# HomeHeat.net
KiCad netlist of a schematic drawn in EAGLE
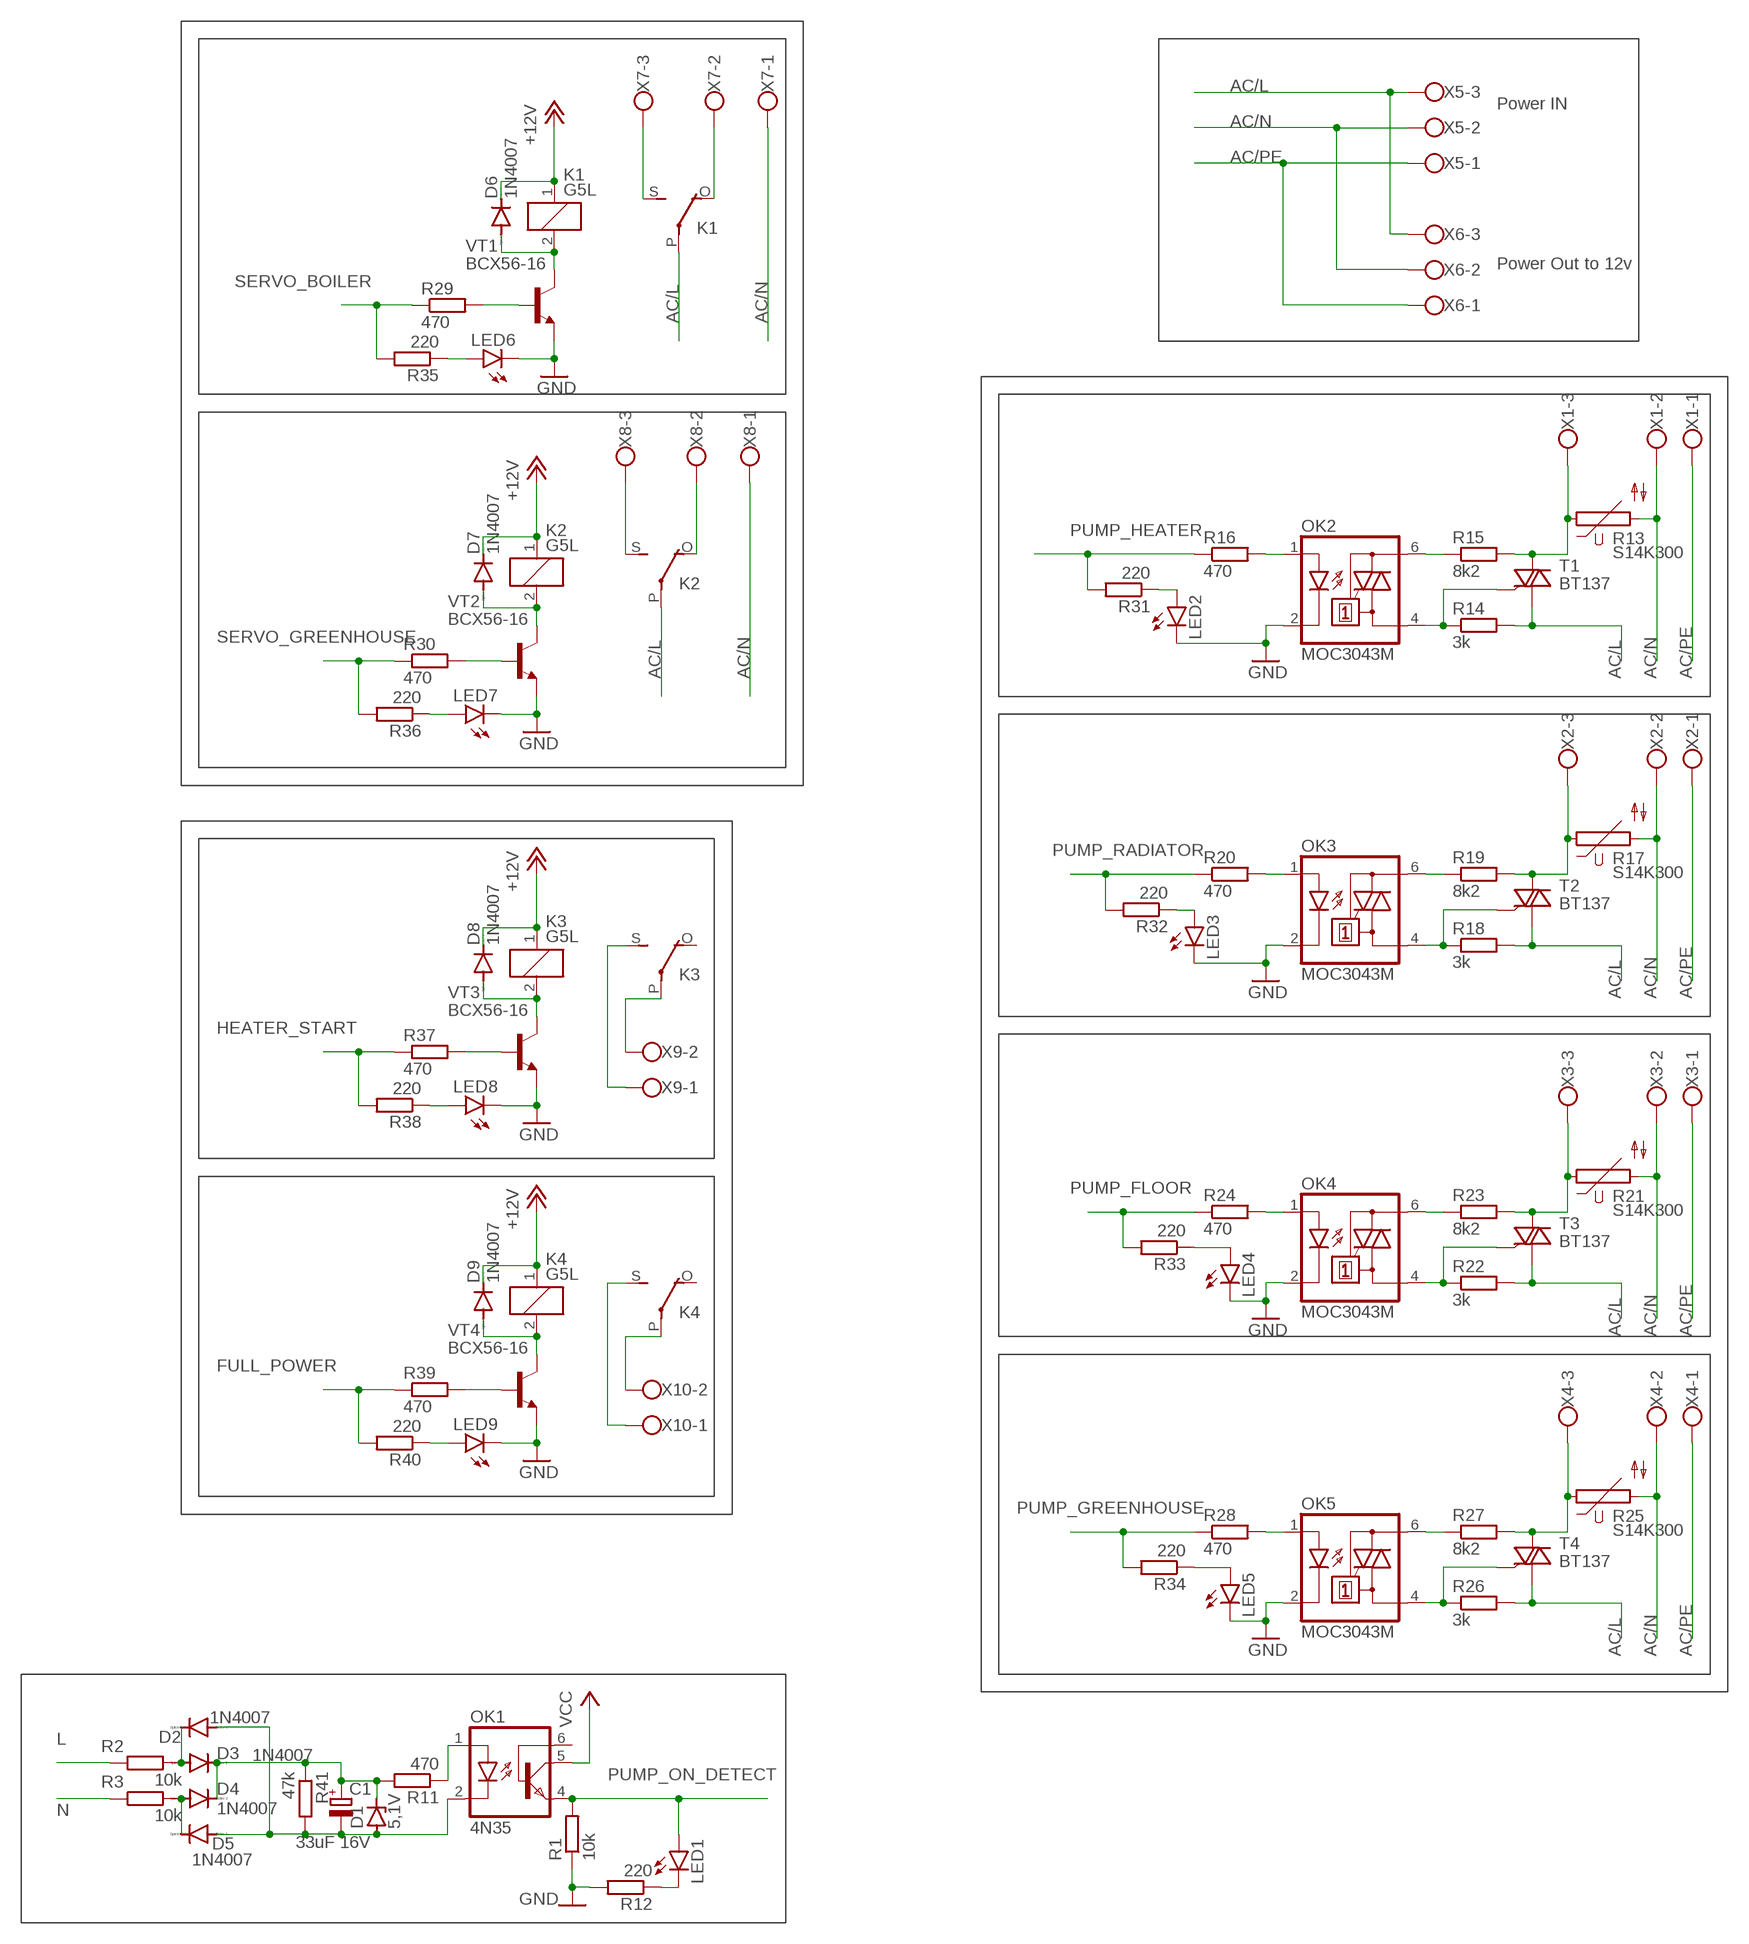
[diagram p0: schematic, sheet 1]

(export (version "E")
  (design (tool "Eeschema 10.0.6"))
  (components
    (comp (ref "C1")
      (value "33uF 16V")
      (footprint "eagle-import:SMC_A")
      (libsource (lib "eagle-import") (part "CPOL-EUSMCA"))
    )
    (comp (ref "D1")
      (value "5,1V")
      (footprint "eagle-import:DO41Z10")
      (libsource (lib "eagle-import") (part "ZENER-DIODEDO41Z10"))
    )
    (comp (ref "D2")
      (value "1N4007")
      (footprint "eagle-import:DO41-10")
      (libsource (lib "eagle-import") (part "1N4004"))
    )
    (comp (ref "D3")
      (value "1N4007")
      (footprint "eagle-import:DO41-10")
      (libsource (lib "eagle-import") (part "1N4004"))
    )
    (comp (ref "D4")
      (value "1N4007")
      (footprint "eagle-import:DO41-10")
      (fields (field (name "SPICEPREFIX") "D"))
      (libsource (lib "eagle-import") (part "1N4004"))
    )
    (comp (ref "D5")
      (value "1N4007")
      (footprint "eagle-import:DO41-10")
      (libsource (lib "eagle-import") (part "1N4004"))
    )
    (comp (ref "D6")
      (value "1N4007")
      (footprint "eagle-import:DO41-10")
      (libsource (lib "eagle-import") (part "1N4004"))
    )
    (comp (ref "D7")
      (value "1N4007")
      (footprint "eagle-import:DO41-10")
      (libsource (lib "eagle-import") (part "1N4004"))
    )
    (comp (ref "D8")
      (value "1N4007")
      (footprint "eagle-import:DO41-10")
      (libsource (lib "eagle-import") (part "1N4004"))
    )
    (comp (ref "D9")
      (value "1N4007")
      (footprint "eagle-import:DO41-10")
      (libsource (lib "eagle-import") (part "1N4004"))
    )
    (comp (ref "K1")
      (value "G5L")
      (footprint "eagle-import:G5LE")
      (libsource (lib "eagle-import") (part "G5L"))
    )
    (comp (ref "K2")
      (value "G5L")
      (footprint "eagle-import:G5LE")
      (libsource (lib "eagle-import") (part "G5L"))
    )
    (comp (ref "K3")
      (value "G5L")
      (footprint "eagle-import:G5LE")
      (libsource (lib "eagle-import") (part "G5L"))
    )
    (comp (ref "K4")
      (value "G5L")
      (footprint "eagle-import:G5LE")
      (libsource (lib "eagle-import") (part "G5L"))
    )
    (comp (ref "LED1")
      (value "LEDCHIP-LED0805")
      (footprint "eagle-import:CHIP-LED0805")
      (libsource (lib "eagle-import") (part "LEDCHIP-LED0805"))
    )
    (comp (ref "LED2")
      (value "LEDCHIP-LED0805")
      (footprint "eagle-import:CHIP-LED0805")
      (libsource (lib "eagle-import") (part "LEDCHIP-LED0805"))
    )
    (comp (ref "LED3")
      (value "LEDCHIP-LED0805")
      (footprint "eagle-import:CHIP-LED0805")
      (libsource (lib "eagle-import") (part "LEDCHIP-LED0805"))
    )
    (comp (ref "LED4")
      (value "LEDCHIP-LED0805")
      (footprint "eagle-import:CHIP-LED0805")
      (libsource (lib "eagle-import") (part "LEDCHIP-LED0805"))
    )
    (comp (ref "LED5")
      (value "LEDCHIP-LED0805")
      (footprint "eagle-import:CHIP-LED0805")
      (libsource (lib "eagle-import") (part "LEDCHIP-LED0805"))
    )
    (comp (ref "LED6")
      (value "LEDCHIP-LED0805")
      (footprint "eagle-import:CHIP-LED0805")
      (libsource (lib "eagle-import") (part "LEDCHIP-LED0805"))
    )
    (comp (ref "LED7")
      (value "LEDCHIP-LED0805")
      (footprint "eagle-import:CHIP-LED0805")
      (libsource (lib "eagle-import") (part "LEDCHIP-LED0805"))
    )
    (comp (ref "LED8")
      (value "LEDCHIP-LED0805")
      (footprint "eagle-import:CHIP-LED0805")
      (libsource (lib "eagle-import") (part "LEDCHIP-LED0805"))
    )
    (comp (ref "LED9")
      (value "LEDCHIP-LED0805")
      (footprint "eagle-import:CHIP-LED0805")
      (libsource (lib "eagle-import") (part "LEDCHIP-LED0805"))
    )
    (comp (ref "OK1")
      (value "4N35")
      (footprint "eagle-import:DIL06")
      (fields (field (name "MF") "FAIRCHILD SEMICONDUCTOR"))
      (libsource (lib "eagle-import") (part "4N35"))
    )
    (comp (ref "OK2")
      (value "MOC3043M")
      (footprint "eagle-import:DIL06")
      (fields (field (name "MF") "FAIRCHILD SEMICONDUCTOR") (field (name "MPN") "MOC3043-M"))
      (libsource (lib "eagle-import") (part "MOC3043M"))
    )
    (comp (ref "OK3")
      (value "MOC3043M")
      (footprint "eagle-import:DIL06")
      (fields (field (name "MF") "FAIRCHILD SEMICONDUCTOR") (field (name "MPN") "MOC3043-M"))
      (libsource (lib "eagle-import") (part "MOC3043M"))
    )
    (comp (ref "OK4")
      (value "MOC3043M")
      (footprint "eagle-import:DIL06")
      (fields (field (name "MF") "FAIRCHILD SEMICONDUCTOR") (field (name "MPN") "MOC3043-M"))
      (libsource (lib "eagle-import") (part "MOC3043M"))
    )
    (comp (ref "OK5")
      (value "MOC3043M")
      (footprint "eagle-import:DIL06")
      (fields (field (name "MF") "FAIRCHILD SEMICONDUCTOR") (field (name "MPN") "MOC3043-M"))
      (libsource (lib "eagle-import") (part "MOC3043M"))
    )
    (comp (ref "R1")
      (value "10k")
      (footprint "eagle-import:R0805")
      (libsource (lib "eagle-import") (part "R-EU_R0805"))
    )
    (comp (ref "R2")
      (value "10k")
      (footprint "eagle-import:0922_22")
      (libsource (lib "eagle-import") (part "R-EU_0922/22"))
    )
    (comp (ref "R3")
      (value "10k")
      (footprint "eagle-import:0922_22")
      (libsource (lib "eagle-import") (part "R-EU_0922/22"))
    )
    (comp (ref "R11")
      (value "470")
      (footprint "eagle-import:R0805")
      (libsource (lib "eagle-import") (part "R-EU_R0805"))
    )
    (comp (ref "R12")
      (value "220")
      (footprint "eagle-import:R0805")
      (libsource (lib "eagle-import") (part "R-EU_R0805"))
    )
    (comp (ref "R13")
      (value "S14K300")
      (footprint "eagle-import:S14K300")
      (libsource (lib "eagle-import") (part "S14K300"))
    )
    (comp (ref "R14")
      (value "3k")
      (footprint "eagle-import:0207_7")
      (libsource (lib "eagle-import") (part "R-EU_0207/7"))
    )
    (comp (ref "R15")
      (value "8k2")
      (footprint "eagle-import:0207_7")
      (libsource (lib "eagle-import") (part "R-EU_0207/7"))
    )
    (comp (ref "R16")
      (value "470")
      (footprint "eagle-import:R0805")
      (libsource (lib "eagle-import") (part "R-EU_R0805"))
    )
    (comp (ref "R17")
      (value "S14K300")
      (footprint "eagle-import:S14K300")
      (libsource (lib "eagle-import") (part "S14K300"))
    )
    (comp (ref "R18")
      (value "3k")
      (footprint "eagle-import:0207_7")
      (libsource (lib "eagle-import") (part "R-EU_0207/7"))
    )
    (comp (ref "R19")
      (value "8k2")
      (footprint "eagle-import:0207_7")
      (libsource (lib "eagle-import") (part "R-EU_0207/7"))
    )
    (comp (ref "R20")
      (value "470")
      (footprint "eagle-import:R0805")
      (libsource (lib "eagle-import") (part "R-EU_R0805"))
    )
    (comp (ref "R21")
      (value "S14K300")
      (footprint "eagle-import:S14K300")
      (libsource (lib "eagle-import") (part "S14K300"))
    )
    (comp (ref "R22")
      (value "3k")
      (footprint "eagle-import:0207_7")
      (libsource (lib "eagle-import") (part "R-EU_0207/7"))
    )
    (comp (ref "R23")
      (value "8k2")
      (footprint "eagle-import:0207_7")
      (libsource (lib "eagle-import") (part "R-EU_0207/7"))
    )
    (comp (ref "R24")
      (value "470")
      (footprint "eagle-import:R0805")
      (libsource (lib "eagle-import") (part "R-EU_R0805"))
    )
    (comp (ref "R25")
      (value "S14K300")
      (footprint "eagle-import:S14K300")
      (libsource (lib "eagle-import") (part "S14K300"))
    )
    (comp (ref "R26")
      (value "3k")
      (footprint "eagle-import:0207_7")
      (libsource (lib "eagle-import") (part "R-EU_0207/7"))
    )
    (comp (ref "R27")
      (value "8k2")
      (footprint "eagle-import:0207_7")
      (libsource (lib "eagle-import") (part "R-EU_0207/7"))
    )
    (comp (ref "R28")
      (value "470")
      (footprint "eagle-import:R0805")
      (libsource (lib "eagle-import") (part "R-EU_R0805"))
    )
    (comp (ref "R29")
      (value "470")
      (footprint "eagle-import:R0805")
      (libsource (lib "eagle-import") (part "R-EU_R0805"))
    )
    (comp (ref "R30")
      (value "470")
      (footprint "eagle-import:R0805")
      (libsource (lib "eagle-import") (part "R-EU_R0805"))
    )
    (comp (ref "R31")
      (value "220")
      (footprint "eagle-import:R0805")
      (libsource (lib "eagle-import") (part "R-EU_R0805"))
    )
    (comp (ref "R32")
      (value "220")
      (footprint "eagle-import:R0805")
      (libsource (lib "eagle-import") (part "R-EU_R0805"))
    )
    (comp (ref "R33")
      (value "220")
      (footprint "eagle-import:R0805")
      (libsource (lib "eagle-import") (part "R-EU_R0805"))
    )
    (comp (ref "R34")
      (value "220")
      (footprint "eagle-import:R0805")
      (libsource (lib "eagle-import") (part "R-EU_R0805"))
    )
    (comp (ref "R35")
      (value "220")
      (footprint "eagle-import:R0805")
      (libsource (lib "eagle-import") (part "R-EU_R0805"))
    )
    (comp (ref "R36")
      (value "220")
      (footprint "eagle-import:R0805")
      (libsource (lib "eagle-import") (part "R-EU_R0805"))
    )
    (comp (ref "R37")
      (value "470")
      (footprint "eagle-import:R0805")
      (libsource (lib "eagle-import") (part "R-EU_R0805"))
    )
    (comp (ref "R38")
      (value "220")
      (footprint "eagle-import:R0805")
      (libsource (lib "eagle-import") (part "R-EU_R0805"))
    )
    (comp (ref "R39")
      (value "470")
      (footprint "eagle-import:R0805")
      (libsource (lib "eagle-import") (part "R-EU_R0805"))
    )
    (comp (ref "R40")
      (value "220")
      (footprint "eagle-import:R0805")
      (libsource (lib "eagle-import") (part "R-EU_R0805"))
    )
    (comp (ref "R41")
      (value "47k")
      (footprint "eagle-import:R0805")
      (libsource (lib "eagle-import") (part "R-EU_R0805"))
    )
    (comp (ref "T1")
      (value "BT137")
      (footprint "eagle-import:TO220AB")
      (libsource (lib "eagle-import") (part "BT136"))
    )
    (comp (ref "T2")
      (value "BT137")
      (footprint "eagle-import:TO220AB")
      (libsource (lib "eagle-import") (part "BT136"))
    )
    (comp (ref "T3")
      (value "BT137")
      (footprint "eagle-import:TO220AB")
      (libsource (lib "eagle-import") (part "BT136"))
    )
    (comp (ref "T4")
      (value "BT137")
      (footprint "eagle-import:TO220AB")
      (libsource (lib "eagle-import") (part "BT136"))
    )
    (comp (ref "VT1")
      (value "BCX56-16")
      (footprint "eagle-import:SOT89-BCE")
      (libsource (lib "eagle-import") (part "BCX56-16"))
    )
    (comp (ref "VT2")
      (value "BCX56-16")
      (footprint "eagle-import:SOT89-BCE")
      (libsource (lib "eagle-import") (part "BCX56-16"))
    )
    (comp (ref "VT3")
      (value "BCX56-16")
      (footprint "eagle-import:SOT89-BCE")
      (libsource (lib "eagle-import") (part "BCX56-16"))
    )
    (comp (ref "VT4")
      (value "BCX56-16")
      (footprint "eagle-import:SOT89-BCE")
      (libsource (lib "eagle-import") (part "BCX56-16"))
    )
    (comp (ref "X1")
      (value "W237-103")
      (footprint "eagle-import:W237-103")
      (fields (field (name "MPN") "237-103"))
      (libsource (lib "eagle-import") (part "W237-103"))
    )
    (comp (ref "X2")
      (value "W237-103")
      (footprint "eagle-import:W237-103")
      (fields (field (name "MPN") "237-103"))
      (libsource (lib "eagle-import") (part "W237-103"))
    )
    (comp (ref "X3")
      (value "W237-103")
      (footprint "eagle-import:W237-103")
      (fields (field (name "MPN") "237-103"))
      (libsource (lib "eagle-import") (part "W237-103"))
    )
    (comp (ref "X4")
      (value "W237-103")
      (footprint "eagle-import:W237-103")
      (fields (field (name "MPN") "237-103"))
      (libsource (lib "eagle-import") (part "W237-103"))
    )
    (comp (ref "X5")
      (value "W237-103")
      (footprint "eagle-import:W237-103")
      (fields (field (name "MPN") "237-103"))
      (libsource (lib "eagle-import") (part "W237-103"))
    )
    (comp (ref "X6")
      (value "W237-103")
      (footprint "eagle-import:W237-103")
      (fields (field (name "MPN") "237-103"))
      (libsource (lib "eagle-import") (part "W237-103"))
    )
    (comp (ref "X7")
      (value "W237-103")
      (footprint "eagle-import:W237-103")
      (fields (field (name "MPN") "237-103"))
      (libsource (lib "eagle-import") (part "W237-103"))
    )
    (comp (ref "X8")
      (value "W237-103")
      (footprint "eagle-import:W237-103")
      (fields (field (name "MPN") "237-103"))
      (libsource (lib "eagle-import") (part "W237-103"))
    )
    (comp (ref "X9")
      (value "W237-102")
      (footprint "eagle-import:W237-102")
      (fields (field (name "MPN") "237-102"))
      (libsource (lib "eagle-import") (part "W237-102"))
    )
    (comp (ref "X10")
      (value "W237-102")
      (footprint "eagle-import:W237-102")
      (fields (field (name "MPN") "237-102"))
      (libsource (lib "eagle-import") (part "W237-102"))
    )
  )
  (nets
    (net (code "1") (name "+12V") (class "Default")
      (node (ref "D6") (pin "C") (pinfunction "C_C") (pintype "passive"))
      (node (ref "D7") (pin "C") (pinfunction "C_C") (pintype "passive"))
      (node (ref "D8") (pin "C") (pinfunction "C_C") (pintype "passive"))
      (node (ref "D9") (pin "C") (pinfunction "C_C") (pintype "passive"))
      (node (ref "K1") (pin "1") (pinfunction "1_1") (pintype "passive"))
      (node (ref "K2") (pin "1") (pinfunction "1_1") (pintype "passive"))
      (node (ref "K3") (pin "1") (pinfunction "1_1") (pintype "passive"))
      (node (ref "K4") (pin "1") (pinfunction "1_1") (pintype "passive"))
    )
    (net (code "2") (name "/AC{slash}L") (class "Default")
      (node (ref "K1") (pin "P") (pinfunction "P_P") (pintype "passive"))
      (node (ref "K2") (pin "P") (pinfunction "P_P") (pintype "passive"))
      (node (ref "R14") (pin "2") (pinfunction "2_2") (pintype "passive"))
      (node (ref "R18") (pin "2") (pinfunction "2_2") (pintype "passive"))
      (node (ref "R22") (pin "2") (pinfunction "2_2") (pintype "passive"))
      (node (ref "R26") (pin "2") (pinfunction "2_2") (pintype "passive"))
      (node (ref "T1") (pin "1") (pinfunction "A1_1") (pintype "passive"))
      (node (ref "T2") (pin "1") (pinfunction "A1_1") (pintype "passive"))
      (node (ref "T3") (pin "1") (pinfunction "A1_1") (pintype "passive"))
      (node (ref "T4") (pin "1") (pinfunction "A1_1") (pintype "passive"))
      (node (ref "X5") (pin "3") (pinfunction "KL_3") (pintype "passive"))
      (node (ref "X6") (pin "3") (pinfunction "KL_3") (pintype "passive"))
    )
    (net (code "3") (name "/AC{slash}N") (class "Default")
      (node (ref "R13") (pin "2") (pinfunction "2_2") (pintype "passive"))
      (node (ref "R17") (pin "2") (pinfunction "2_2") (pintype "passive"))
      (node (ref "R21") (pin "2") (pinfunction "2_2") (pintype "passive"))
      (node (ref "R25") (pin "2") (pinfunction "2_2") (pintype "passive"))
      (node (ref "X1") (pin "2") (pinfunction "KL_2") (pintype "passive"))
      (node (ref "X2") (pin "2") (pinfunction "KL_2") (pintype "passive"))
      (node (ref "X3") (pin "2") (pinfunction "KL_2") (pintype "passive"))
      (node (ref "X4") (pin "2") (pinfunction "KL_2") (pintype "passive"))
      (node (ref "X5") (pin "2") (pinfunction "KL_2") (pintype "passive"))
      (node (ref "X6") (pin "2") (pinfunction "KL_2") (pintype "passive"))
      (node (ref "X7") (pin "1") (pinfunction "KL_1") (pintype "passive"))
      (node (ref "X8") (pin "1") (pinfunction "KL_1") (pintype "passive"))
    )
    (net (code "4") (name "/AC{slash}PE") (class "Default")
      (node (ref "X1") (pin "1") (pinfunction "KL_1") (pintype "passive"))
      (node (ref "X2") (pin "1") (pinfunction "KL_1") (pintype "passive"))
      (node (ref "X3") (pin "1") (pinfunction "KL_1") (pintype "passive"))
      (node (ref "X4") (pin "1") (pinfunction "KL_1") (pintype "passive"))
      (node (ref "X5") (pin "1") (pinfunction "KL_1") (pintype "passive"))
      (node (ref "X6") (pin "1") (pinfunction "KL_1") (pintype "passive"))
    )
    (net (code "5") (name "/FULL_POWER") (class "Default")
      (node (ref "R39") (pin "1") (pinfunction "1_1") (pintype "passive"))
      (node (ref "R40") (pin "2") (pinfunction "2_2") (pintype "passive"))
    )
    (net (code "6") (name "/HEATER_START") (class "Default")
      (node (ref "R37") (pin "1") (pinfunction "1_1") (pintype "passive"))
      (node (ref "R38") (pin "2") (pinfunction "2_2") (pintype "passive"))
    )
    (net (code "7") (name "/PUMP_FLOOR") (class "Default")
      (node (ref "R24") (pin "1") (pinfunction "1_1") (pintype "passive"))
      (node (ref "R33") (pin "2") (pinfunction "2_2") (pintype "passive"))
    )
    (net (code "8") (name "/PUMP_GREENHOUSE") (class "Default")
      (node (ref "R28") (pin "1") (pinfunction "1_1") (pintype "passive"))
      (node (ref "R34") (pin "2") (pinfunction "2_2") (pintype "passive"))
    )
    (net (code "9") (name "/PUMP_HEATER") (class "Default")
      (node (ref "R16") (pin "1") (pinfunction "1_1") (pintype "passive"))
      (node (ref "R31") (pin "2") (pinfunction "2_2") (pintype "passive"))
    )
    (net (code "10") (name "/PUMP_ON_DETECT") (class "Default")
      (node (ref "LED1") (pin "A") (pinfunction "A_A") (pintype "passive"))
      (node (ref "OK1") (pin "4") (pinfunction "EMI_4") (pintype "passive"))
      (node (ref "R1") (pin "2") (pinfunction "2_2") (pintype "passive"))
    )
    (net (code "11") (name "/PUMP_RADIATOR") (class "Default")
      (node (ref "R20") (pin "1") (pinfunction "1_1") (pintype "passive"))
      (node (ref "R32") (pin "2") (pinfunction "2_2") (pintype "passive"))
    )
    (net (code "12") (name "/SERVO_BOILER") (class "Default")
      (node (ref "R29") (pin "1") (pinfunction "1_1") (pintype "passive"))
      (node (ref "R35") (pin "2") (pinfunction "2_2") (pintype "passive"))
    )
    (net (code "13") (name "/SERVO_GREENHOUSE") (class "Default")
      (node (ref "R30") (pin "1") (pinfunction "1_1") (pintype "passive"))
      (node (ref "R36") (pin "2") (pinfunction "2_2") (pintype "passive"))
    )
    (net (code "14") (name "GND") (class "Default")
      (node (ref "LED2") (pin "C") (pinfunction "C_C") (pintype "passive"))
      (node (ref "LED3") (pin "C") (pinfunction "C_C") (pintype "passive"))
      (node (ref "LED4") (pin "C") (pinfunction "C_C") (pintype "passive"))
      (node (ref "LED5") (pin "C") (pinfunction "C_C") (pintype "passive"))
      (node (ref "LED6") (pin "C") (pinfunction "C_C") (pintype "passive"))
      (node (ref "LED7") (pin "C") (pinfunction "C_C") (pintype "passive"))
      (node (ref "LED8") (pin "C") (pinfunction "C_C") (pintype "passive"))
      (node (ref "LED9") (pin "C") (pinfunction "C_C") (pintype "passive"))
      (node (ref "OK2") (pin "2") (pinfunction "C_2") (pintype "passive"))
      (node (ref "OK3") (pin "2") (pinfunction "C_2") (pintype "passive"))
      (node (ref "OK4") (pin "2") (pinfunction "C_2") (pintype "passive"))
      (node (ref "OK5") (pin "2") (pinfunction "C_2") (pintype "passive"))
      (node (ref "R1") (pin "1") (pinfunction "1_1") (pintype "passive"))
      (node (ref "R12") (pin "2") (pinfunction "2_2") (pintype "passive"))
      (node (ref "VT1") (pin "E") (pinfunction "E_E") (pintype "passive"))
      (node (ref "VT2") (pin "E") (pinfunction "E_E") (pintype "passive"))
      (node (ref "VT3") (pin "E") (pinfunction "E_E") (pintype "passive"))
      (node (ref "VT4") (pin "E") (pinfunction "E_E") (pintype "passive"))
    )
    (net (code "15") (name "Net-(C1-Pad+)") (class "Default")
      (node (ref "C1") (pin "+") (pinfunction "+_+") (pintype "passive"))
      (node (ref "D1") (pin "C") (pinfunction "C_C") (pintype "passive"))
      (node (ref "D3") (pin "C") (pinfunction "C_C") (pintype "passive"))
      (node (ref "D4") (pin "C") (pinfunction "C_C") (pintype "passive"))
      (node (ref "R11") (pin "2") (pinfunction "2_2") (pintype "passive"))
      (node (ref "R41") (pin "1") (pinfunction "1_1") (pintype "passive"))
    )
    (net (code "16") (name "Net-(D2-PadC)") (class "Default")
      (node (ref "D2") (pin "C") (pinfunction "C_C") (pintype "passive"))
      (node (ref "D3") (pin "A") (pinfunction "A_A") (pintype "passive"))
      (node (ref "R2") (pin "2") (pinfunction "2_2") (pintype "passive"))
    )
    (net (code "17") (name "Net-(D4-PadA)") (class "Default")
      (node (ref "D4") (pin "A") (pinfunction "A_A") (pintype "passive"))
      (node (ref "D5") (pin "C") (pinfunction "C_C") (pintype "passive"))
      (node (ref "R3") (pin "2") (pinfunction "2_2") (pintype "passive"))
    )
    (net (code "18") (name "Net-(D6-PadA)") (class "Default")
      (node (ref "D6") (pin "A") (pinfunction "A_A") (pintype "passive"))
      (node (ref "K1") (pin "2") (pinfunction "2_2") (pintype "passive"))
      (node (ref "VT1") (pin "C") (pinfunction "C_C") (pintype "passive"))
      (node (ref "VT1") (pin "C@1") (pinfunction "C_C@1") (pintype "passive"))
    )
    (net (code "19") (name "Net-(D7-PadA)") (class "Default")
      (node (ref "D7") (pin "A") (pinfunction "A_A") (pintype "passive"))
      (node (ref "K2") (pin "2") (pinfunction "2_2") (pintype "passive"))
      (node (ref "VT2") (pin "C") (pinfunction "C_C") (pintype "passive"))
      (node (ref "VT2") (pin "C@1") (pinfunction "C_C@1") (pintype "passive"))
    )
    (net (code "20") (name "Net-(D8-PadA)") (class "Default")
      (node (ref "D8") (pin "A") (pinfunction "A_A") (pintype "passive"))
      (node (ref "K3") (pin "2") (pinfunction "2_2") (pintype "passive"))
      (node (ref "VT3") (pin "C") (pinfunction "C_C") (pintype "passive"))
      (node (ref "VT3") (pin "C@1") (pinfunction "C_C@1") (pintype "passive"))
    )
    (net (code "21") (name "Net-(D9-PadA)") (class "Default")
      (node (ref "D9") (pin "A") (pinfunction "A_A") (pintype "passive"))
      (node (ref "K4") (pin "2") (pinfunction "2_2") (pintype "passive"))
      (node (ref "VT4") (pin "C") (pinfunction "C_C") (pintype "passive"))
      (node (ref "VT4") (pin "C@1") (pinfunction "C_C@1") (pintype "passive"))
    )
    (net (code "22") (name "Net-(LED1-PadC)") (class "Default")
      (node (ref "LED1") (pin "C") (pinfunction "C_C") (pintype "passive"))
      (node (ref "R12") (pin "1") (pinfunction "1_1") (pintype "passive"))
    )
    (net (code "23") (name "Net-(LED2-PadA)") (class "Default")
      (node (ref "LED2") (pin "A") (pinfunction "A_A") (pintype "passive"))
      (node (ref "R31") (pin "1") (pinfunction "1_1") (pintype "passive"))
    )
    (net (code "24") (name "Net-(LED3-PadA)") (class "Default")
      (node (ref "LED3") (pin "A") (pinfunction "A_A") (pintype "passive"))
      (node (ref "R32") (pin "1") (pinfunction "1_1") (pintype "passive"))
    )
    (net (code "25") (name "Net-(LED4-PadA)") (class "Default")
      (node (ref "LED4") (pin "A") (pinfunction "A_A") (pintype "passive"))
      (node (ref "R33") (pin "1") (pinfunction "1_1") (pintype "passive"))
    )
    (net (code "26") (name "Net-(LED5-PadA)") (class "Default")
      (node (ref "LED5") (pin "A") (pinfunction "A_A") (pintype "passive"))
      (node (ref "R34") (pin "1") (pinfunction "1_1") (pintype "passive"))
    )
    (net (code "27") (name "Net-(LED6-PadA)") (class "Default")
      (node (ref "LED6") (pin "A") (pinfunction "A_A") (pintype "passive"))
      (node (ref "R35") (pin "1") (pinfunction "1_1") (pintype "passive"))
    )
    (net (code "28") (name "Net-(LED7-PadA)") (class "Default")
      (node (ref "LED7") (pin "A") (pinfunction "A_A") (pintype "passive"))
      (node (ref "R36") (pin "1") (pinfunction "1_1") (pintype "passive"))
    )
    (net (code "29") (name "Net-(LED8-PadA)") (class "Default")
      (node (ref "LED8") (pin "A") (pinfunction "A_A") (pintype "passive"))
      (node (ref "R38") (pin "1") (pinfunction "1_1") (pintype "passive"))
    )
    (net (code "30") (name "Net-(LED9-PadA)") (class "Default")
      (node (ref "LED9") (pin "A") (pinfunction "A_A") (pintype "passive"))
      (node (ref "R40") (pin "1") (pinfunction "1_1") (pintype "passive"))
    )
    (net (code "31") (name "Net-(OK1-A)") (class "Default")
      (node (ref "OK1") (pin "1") (pinfunction "A_1") (pintype "passive"))
      (node (ref "R11") (pin "1") (pinfunction "1_1") (pintype "passive"))
    )
    (net (code "32") (name "Net-(OK1-C)") (class "Default")
      (node (ref "C1") (pin "-") (pinfunction "-_-") (pintype "passive"))
      (node (ref "D1") (pin "A") (pinfunction "A_A") (pintype "passive"))
      (node (ref "D2") (pin "A") (pinfunction "A_A") (pintype "passive"))
      (node (ref "D5") (pin "A") (pinfunction "A_A") (pintype "passive"))
      (node (ref "OK1") (pin "2") (pinfunction "C_2") (pintype "passive"))
      (node (ref "R41") (pin "2") (pinfunction "2_2") (pintype "passive"))
    )
    (net (code "33") (name "Net-(OK2-A)") (class "Default")
      (node (ref "OK2") (pin "1") (pinfunction "A_1") (pintype "passive"))
      (node (ref "R16") (pin "2") (pinfunction "2_2") (pintype "passive"))
    )
    (net (code "34") (name "Net-(OK2-A1)") (class "Default")
      (node (ref "OK2") (pin "4") (pinfunction "A1_4") (pintype "passive"))
      (node (ref "R14") (pin "1") (pinfunction "1_1") (pintype "passive"))
      (node (ref "T1") (pin "3") (pinfunction "G_3") (pintype "passive"))
    )
    (net (code "35") (name "Net-(OK2-A2)") (class "Default")
      (node (ref "OK2") (pin "6") (pinfunction "A2_6") (pintype "passive"))
      (node (ref "R15") (pin "1") (pinfunction "1_1") (pintype "passive"))
    )
    (net (code "36") (name "Net-(OK3-A)") (class "Default")
      (node (ref "OK3") (pin "1") (pinfunction "A_1") (pintype "passive"))
      (node (ref "R20") (pin "2") (pinfunction "2_2") (pintype "passive"))
    )
    (net (code "37") (name "Net-(OK3-A1)") (class "Default")
      (node (ref "OK3") (pin "4") (pinfunction "A1_4") (pintype "passive"))
      (node (ref "R18") (pin "1") (pinfunction "1_1") (pintype "passive"))
      (node (ref "T2") (pin "3") (pinfunction "G_3") (pintype "passive"))
    )
    (net (code "38") (name "Net-(OK3-A2)") (class "Default")
      (node (ref "OK3") (pin "6") (pinfunction "A2_6") (pintype "passive"))
      (node (ref "R19") (pin "1") (pinfunction "1_1") (pintype "passive"))
    )
    (net (code "39") (name "Net-(OK4-A)") (class "Default")
      (node (ref "OK4") (pin "1") (pinfunction "A_1") (pintype "passive"))
      (node (ref "R24") (pin "2") (pinfunction "2_2") (pintype "passive"))
    )
    (net (code "40") (name "Net-(OK4-A1)") (class "Default")
      (node (ref "OK4") (pin "4") (pinfunction "A1_4") (pintype "passive"))
      (node (ref "R22") (pin "1") (pinfunction "1_1") (pintype "passive"))
      (node (ref "T3") (pin "3") (pinfunction "G_3") (pintype "passive"))
    )
    (net (code "41") (name "Net-(OK4-A2)") (class "Default")
      (node (ref "OK4") (pin "6") (pinfunction "A2_6") (pintype "passive"))
      (node (ref "R23") (pin "1") (pinfunction "1_1") (pintype "passive"))
    )
    (net (code "42") (name "Net-(OK5-A)") (class "Default")
      (node (ref "OK5") (pin "1") (pinfunction "A_1") (pintype "passive"))
      (node (ref "R28") (pin "2") (pinfunction "2_2") (pintype "passive"))
    )
    (net (code "43") (name "Net-(OK5-A1)") (class "Default")
      (node (ref "OK5") (pin "4") (pinfunction "A1_4") (pintype "passive"))
      (node (ref "R26") (pin "1") (pinfunction "1_1") (pintype "passive"))
      (node (ref "T4") (pin "3") (pinfunction "G_3") (pintype "passive"))
    )
    (net (code "44") (name "Net-(OK5-A2)") (class "Default")
      (node (ref "OK5") (pin "6") (pinfunction "A2_6") (pintype "passive"))
      (node (ref "R27") (pin "1") (pinfunction "1_1") (pintype "passive"))
    )
    (net (code "45") (name "Net-(R29-Pad2)") (class "Default")
      (node (ref "R29") (pin "2") (pinfunction "2_2") (pintype "passive"))
      (node (ref "VT1") (pin "B") (pinfunction "B_B") (pintype "passive"))
    )
    (net (code "46") (name "Net-(R30-Pad2)") (class "Default")
      (node (ref "R30") (pin "2") (pinfunction "2_2") (pintype "passive"))
      (node (ref "VT2") (pin "B") (pinfunction "B_B") (pintype "passive"))
    )
    (net (code "47") (name "Net-(R37-Pad2)") (class "Default")
      (node (ref "R37") (pin "2") (pinfunction "2_2") (pintype "passive"))
      (node (ref "VT3") (pin "B") (pinfunction "B_B") (pintype "passive"))
    )
    (net (code "48") (name "Net-(R39-Pad2)") (class "Default")
      (node (ref "R39") (pin "2") (pinfunction "2_2") (pintype "passive"))
      (node (ref "VT4") (pin "B") (pinfunction "B_B") (pintype "passive"))
    )
    (net (code "49") (name "Net-(T1-A2)") (class "Default")
      (node (ref "R13") (pin "1") (pinfunction "1_1") (pintype "passive"))
      (node (ref "R15") (pin "2") (pinfunction "2_2") (pintype "passive"))
      (node (ref "T1") (pin "2") (pinfunction "A2_2") (pintype "passive"))
      (node (ref "X1") (pin "3") (pinfunction "KL_3") (pintype "passive"))
    )
    (net (code "50") (name "Net-(T2-A2)") (class "Default")
      (node (ref "R17") (pin "1") (pinfunction "1_1") (pintype "passive"))
      (node (ref "R19") (pin "2") (pinfunction "2_2") (pintype "passive"))
      (node (ref "T2") (pin "2") (pinfunction "A2_2") (pintype "passive"))
      (node (ref "X2") (pin "3") (pinfunction "KL_3") (pintype "passive"))
    )
    (net (code "51") (name "Net-(T3-A2)") (class "Default")
      (node (ref "R21") (pin "1") (pinfunction "1_1") (pintype "passive"))
      (node (ref "R23") (pin "2") (pinfunction "2_2") (pintype "passive"))
      (node (ref "T3") (pin "2") (pinfunction "A2_2") (pintype "passive"))
      (node (ref "X3") (pin "3") (pinfunction "KL_3") (pintype "passive"))
    )
    (net (code "52") (name "Net-(T4-A2)") (class "Default")
      (node (ref "R25") (pin "1") (pinfunction "1_1") (pintype "passive"))
      (node (ref "R27") (pin "2") (pinfunction "2_2") (pintype "passive"))
      (node (ref "T4") (pin "2") (pinfunction "A2_2") (pintype "passive"))
      (node (ref "X4") (pin "3") (pinfunction "KL_3") (pintype "passive"))
    )
    (net (code "53") (name "Net-(X7B-KL)") (class "Default")
      (node (ref "K1") (pin "O") (pinfunction "O_O") (pintype "passive"))
      (node (ref "X7") (pin "2") (pinfunction "KL_2") (pintype "passive"))
    )
    (net (code "54") (name "Net-(X7C-KL)") (class "Default")
      (node (ref "K1") (pin "S") (pinfunction "S_S") (pintype "passive"))
      (node (ref "X7") (pin "3") (pinfunction "KL_3") (pintype "passive"))
    )
    (net (code "55") (name "Net-(X8B-KL)") (class "Default")
      (node (ref "K2") (pin "O") (pinfunction "O_O") (pintype "passive"))
      (node (ref "X8") (pin "2") (pinfunction "KL_2") (pintype "passive"))
    )
    (net (code "56") (name "Net-(X8C-KL)") (class "Default")
      (node (ref "K2") (pin "S") (pinfunction "S_S") (pintype "passive"))
      (node (ref "X8") (pin "3") (pinfunction "KL_3") (pintype "passive"))
    )
    (net (code "57") (name "Net-(X9A-KL)") (class "Default")
      (node (ref "K3") (pin "S") (pinfunction "S_S") (pintype "passive"))
      (node (ref "X9") (pin "1") (pinfunction "KL_1") (pintype "passive"))
    )
    (net (code "58") (name "Net-(X9B-KL)") (class "Default")
      (node (ref "K3") (pin "P") (pinfunction "P_P") (pintype "passive"))
      (node (ref "X9") (pin "2") (pinfunction "KL_2") (pintype "passive"))
    )
    (net (code "59") (name "Net-(X10A-KL)") (class "Default")
      (node (ref "K4") (pin "S") (pinfunction "S_S") (pintype "passive"))
      (node (ref "X10") (pin "1") (pinfunction "KL_1") (pintype "passive"))
    )
    (net (code "60") (name "Net-(X10B-KL)") (class "Default")
      (node (ref "K4") (pin "P") (pinfunction "P_P") (pintype "passive"))
      (node (ref "X10") (pin "2") (pinfunction "KL_2") (pintype "passive"))
    )
    (net (code "61") (name "VCC") (class "Default")
      (node (ref "OK1") (pin "5") (pinfunction "COL_5") (pintype "passive"))
    )
    (net (code "62") (name "unconnected-(K3-PadO)") (class "Default")
      (node (ref "K3") (pin "O") (pinfunction "O_O") (pintype "passive"))
    )
    (net (code "63") (name "unconnected-(K4-PadO)") (class "Default")
      (node (ref "K4") (pin "O") (pinfunction "O_O") (pintype "passive"))
    )
    (net (code "64") (name "unconnected-(OK1-BAS-Pad6)") (class "Default")
      (node (ref "OK1") (pin "6") (pinfunction "BAS_6") (pintype "passive"))
    )
    (net (code "65") (name "unconnected-(R2-Pad1)") (class "Default")
      (node (ref "R2") (pin "1") (pinfunction "1_1") (pintype "passive"))
    )
    (net (code "66") (name "unconnected-(R3-Pad1)") (class "Default")
      (node (ref "R3") (pin "1") (pinfunction "1_1") (pintype "passive"))
    )
  )
)
